# ETHERUNO.net
KiCad netlist of a schematic drawn in EAGLE
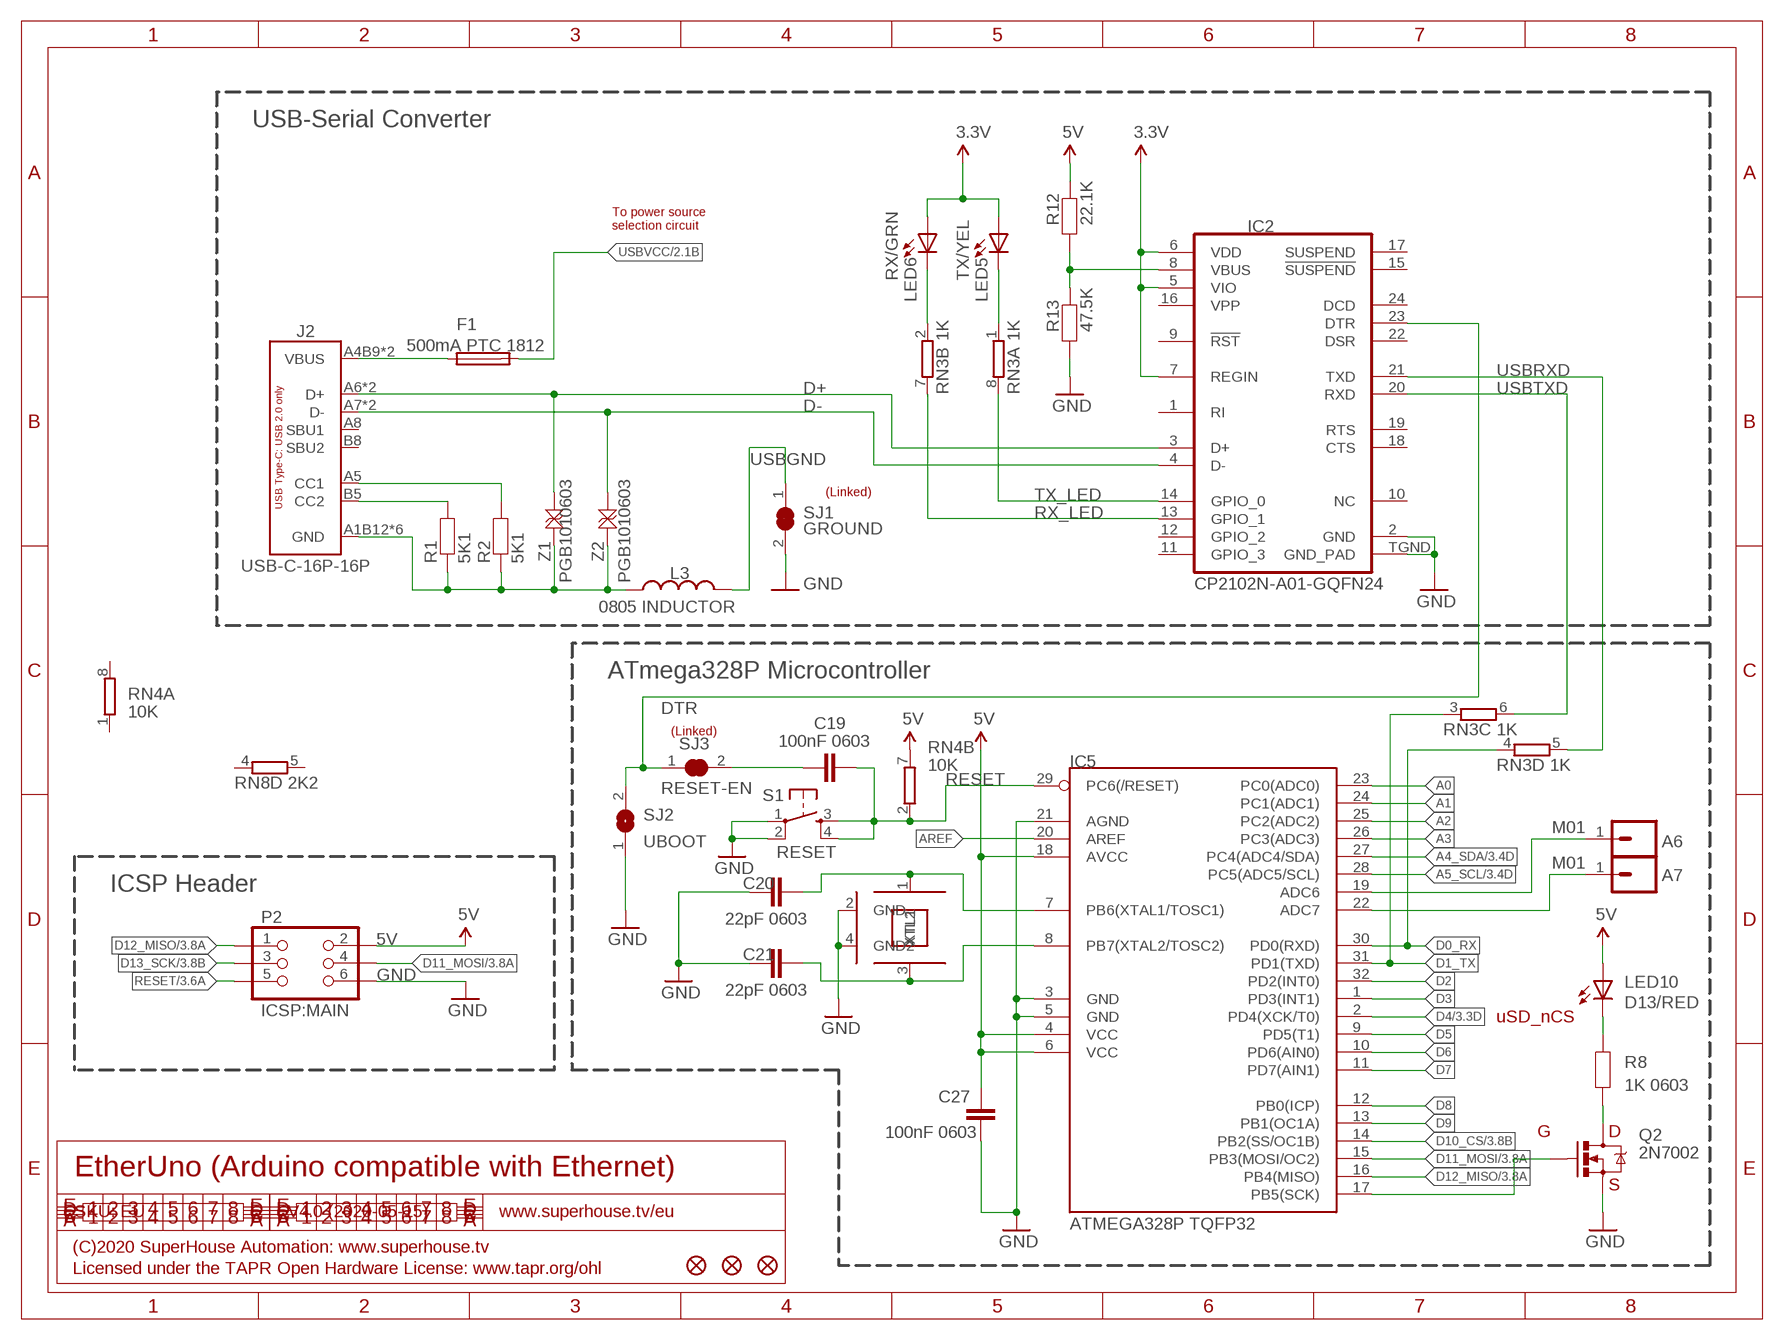
[diagram p0: schematic, sheet 1]
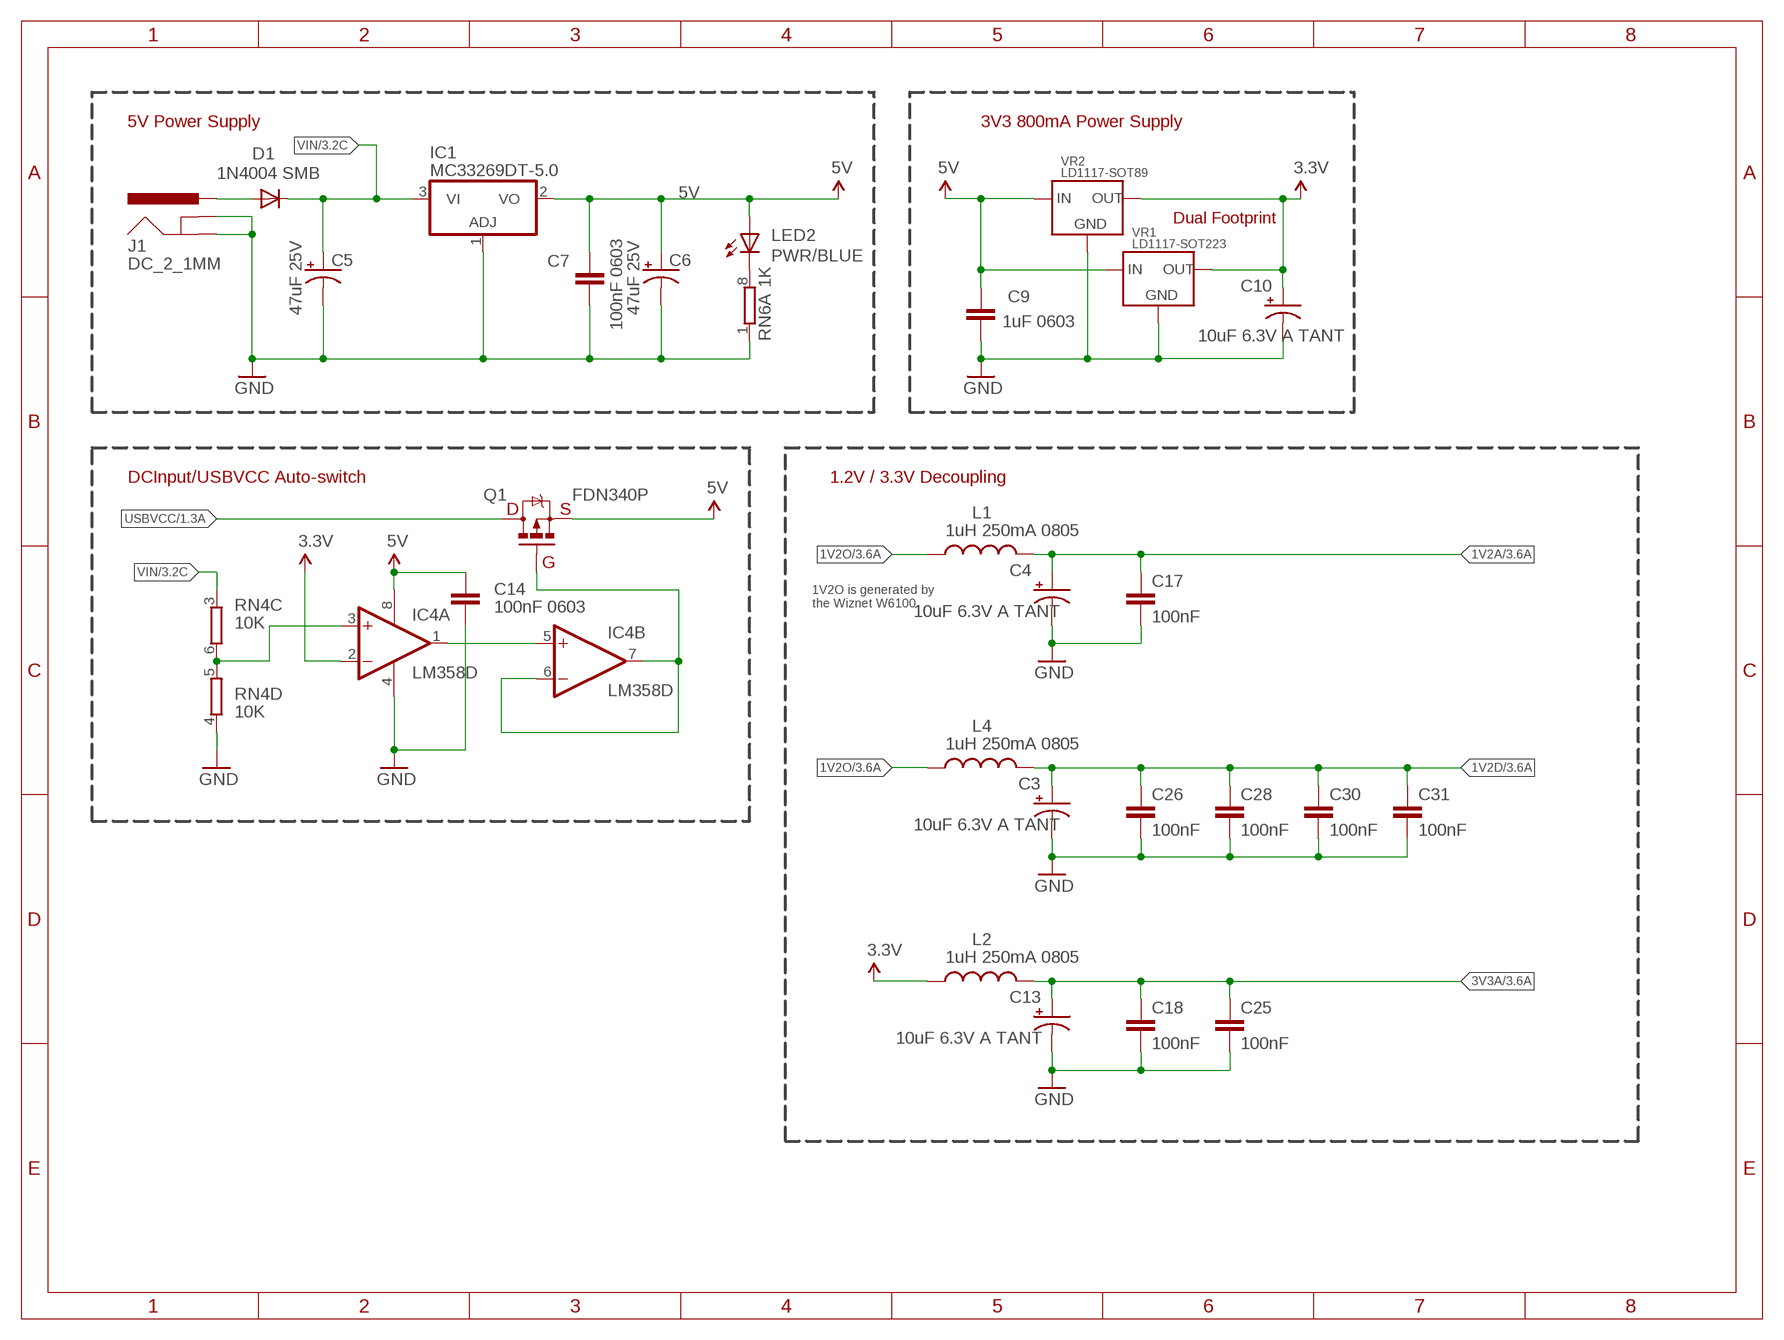
[diagram p1: schematic, sheet 2]
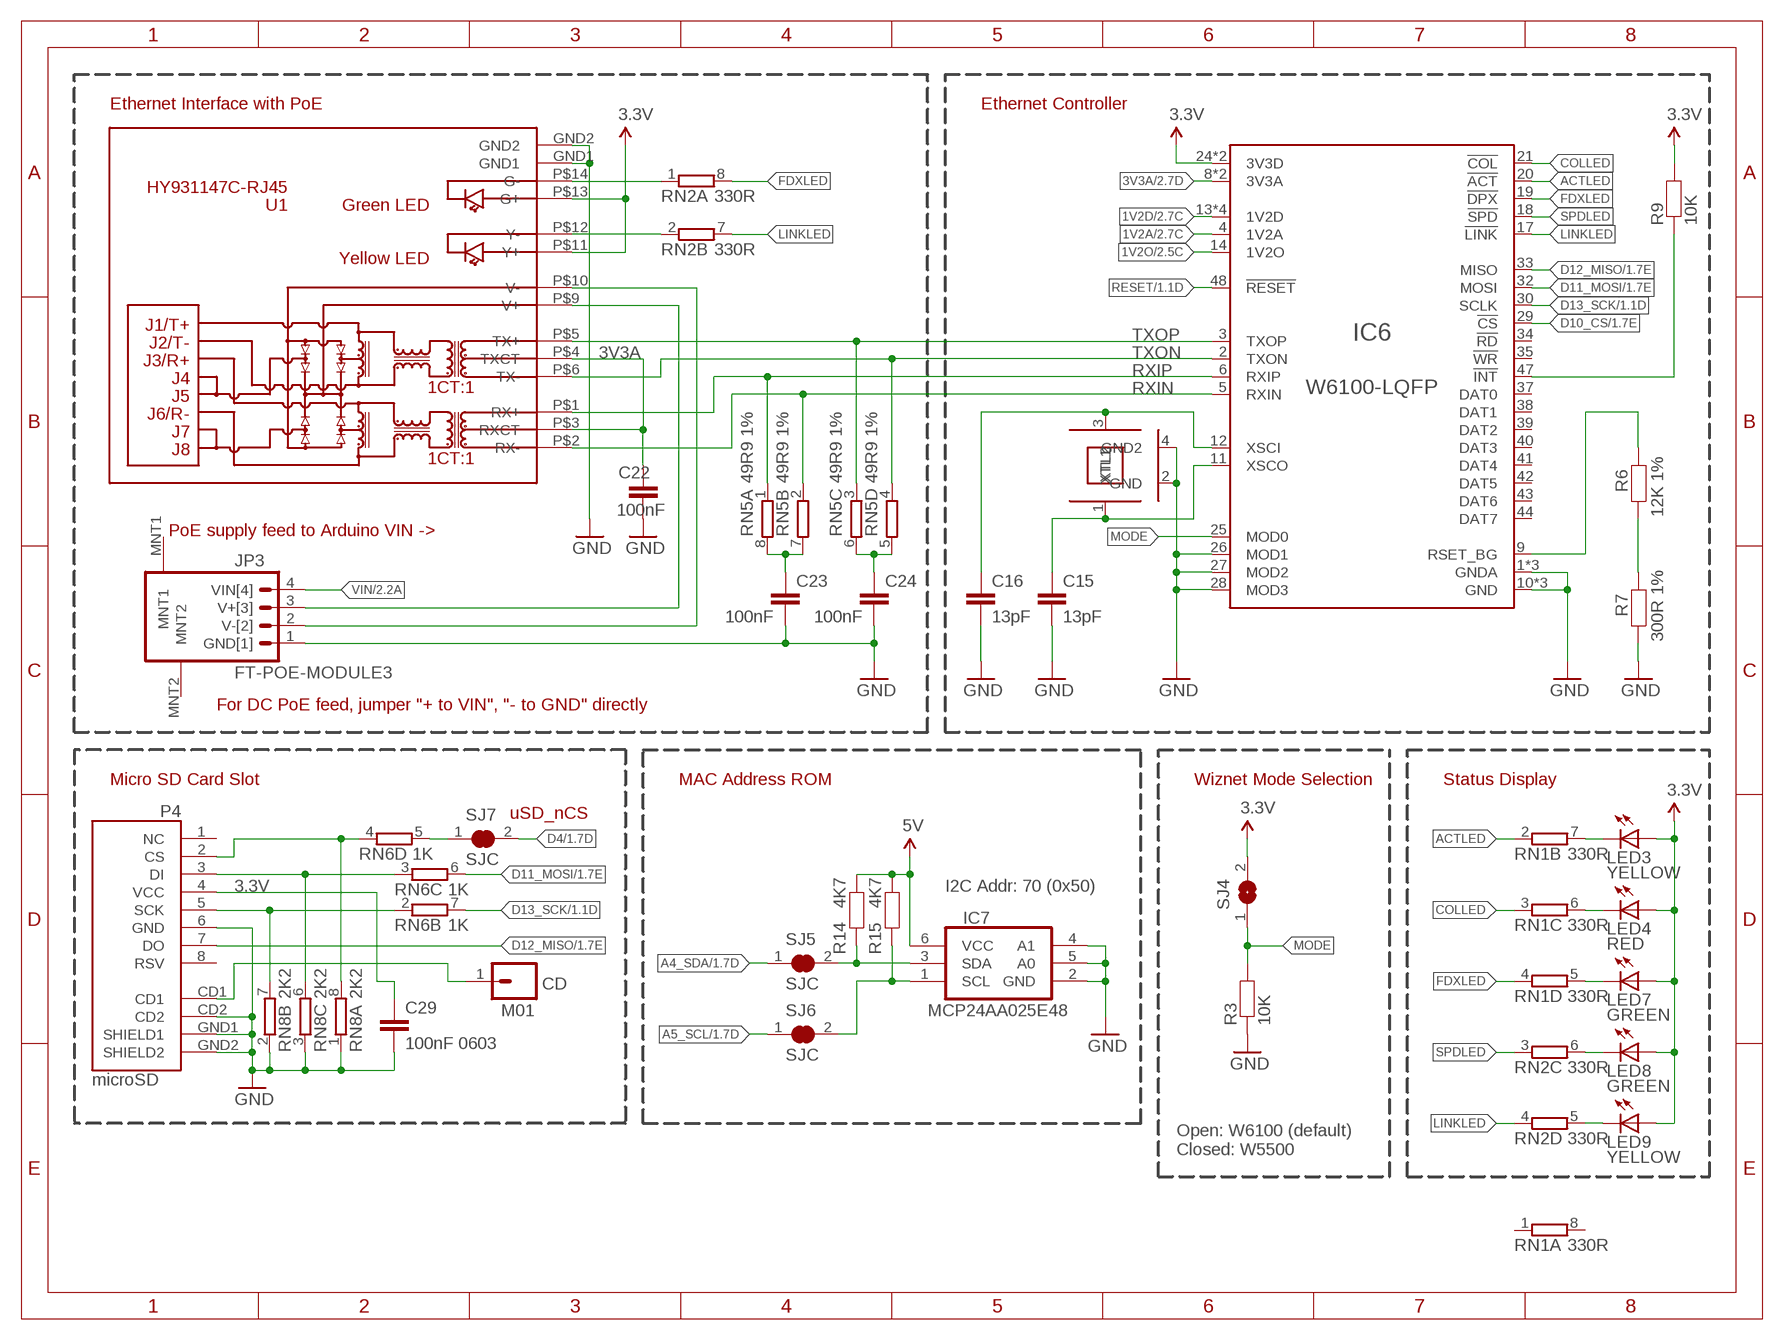
[diagram p2: schematic, sheet 3]
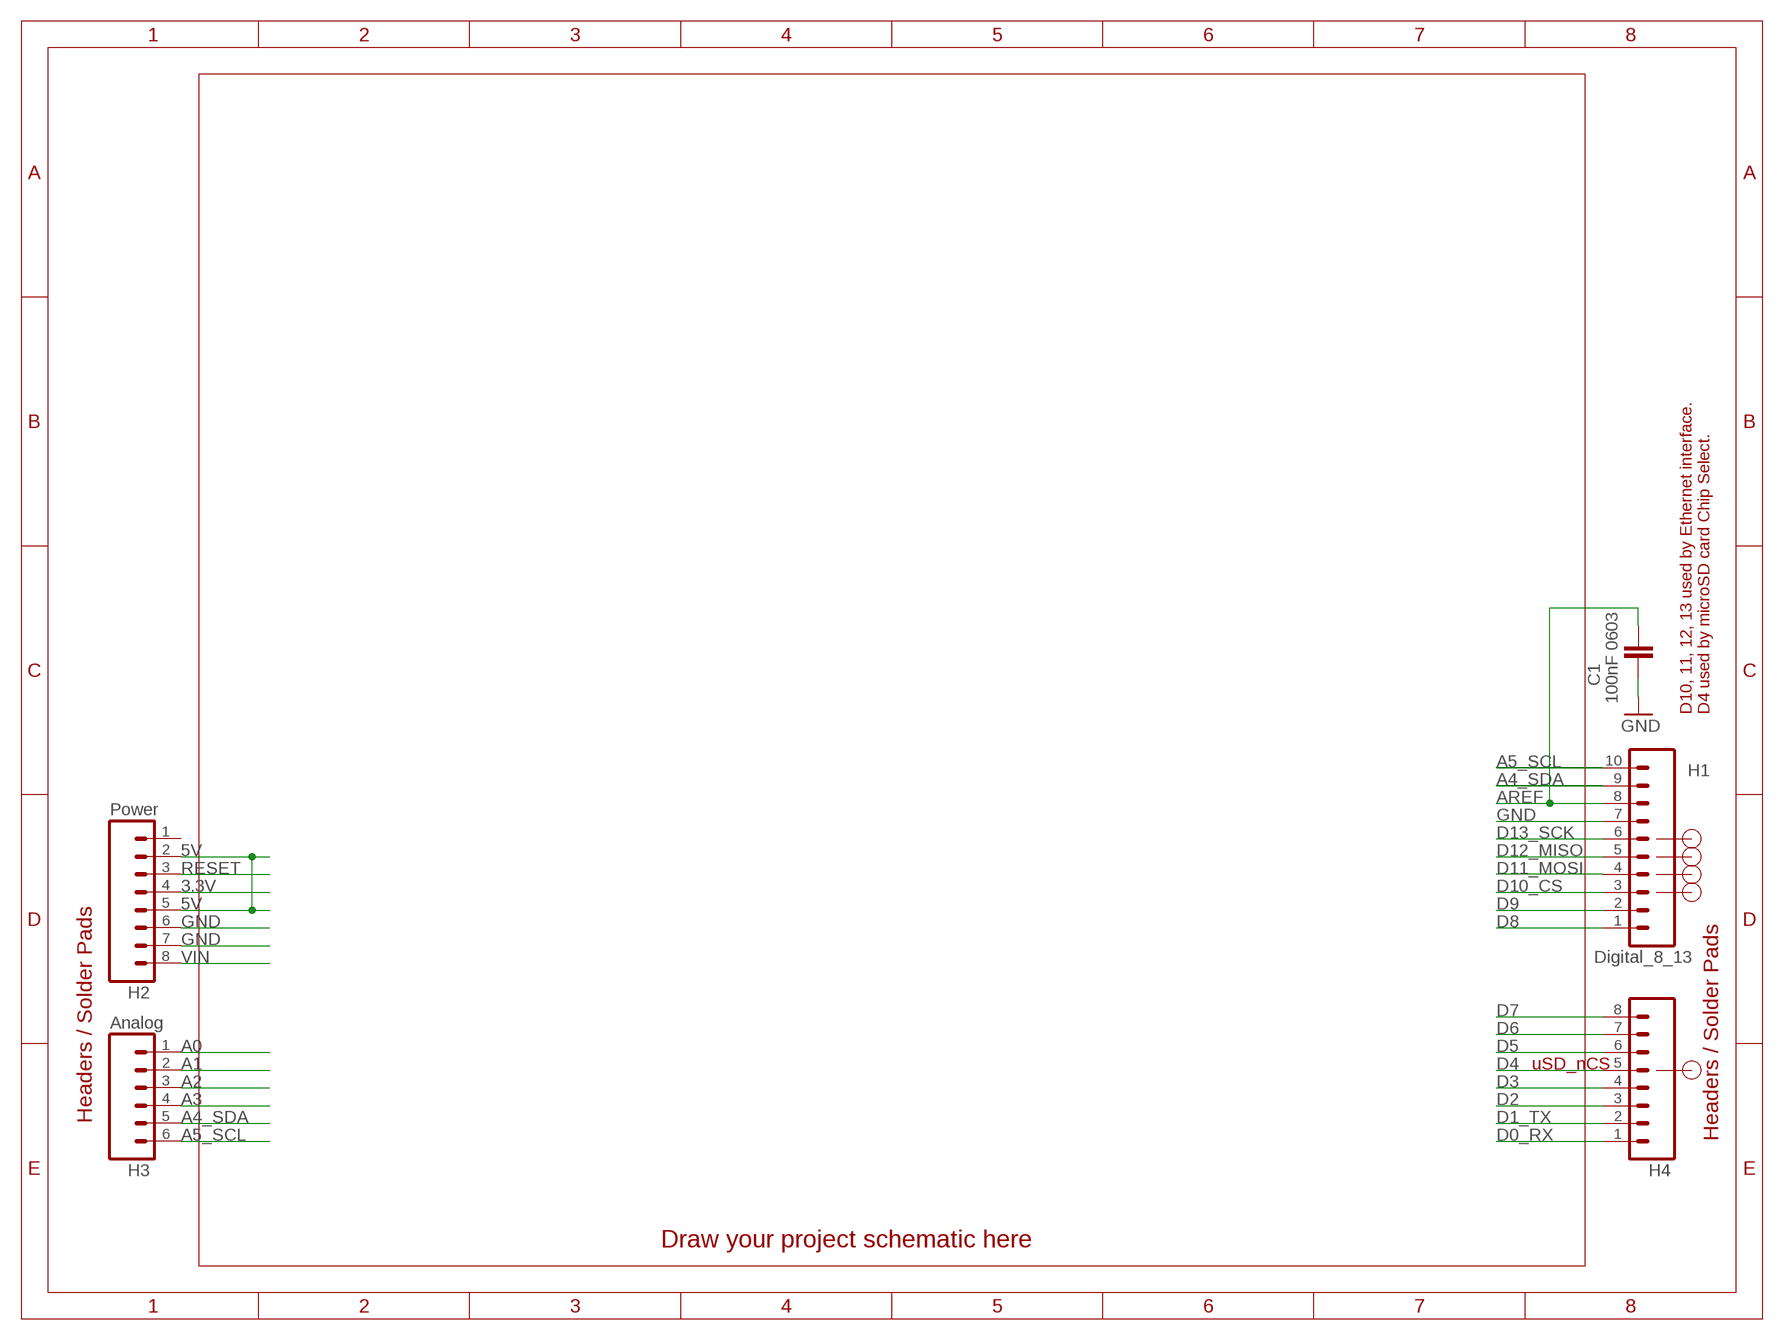
[diagram p3: schematic, sheet 4]

(export (version "E")
  (design (tool "Eeschema 10.0.6"))
  (components
    (comp (ref "A6")
      (value "M01")
      (footprint "eagle-import:1X01")
      (libsource (lib "eagle-import") (part "M01-PLAIN"))
    )
    (comp (ref "A7")
      (value "M01")
      (footprint "eagle-import:1X01")
      (libsource (lib "eagle-import") (part "M01-PLAIN"))
    )
    (comp (ref "C19")
      (value "100nF 0603")
      (footprint "eagle-import:C0603")
      (libsource (lib "eagle-import") (part "CAP0603"))
    )
    (comp (ref "C20")
      (value "22pF 0603")
      (footprint "eagle-import:C0603")
      (libsource (lib "eagle-import") (part "CAP0603"))
    )
    (comp (ref "C21")
      (value "22pF 0603")
      (footprint "eagle-import:C0603")
      (libsource (lib "eagle-import") (part "CAP0603"))
    )
    (comp (ref "C27")
      (value "100nF 0603")
      (footprint "eagle-import:C0603")
      (libsource (lib "eagle-import") (part "CAP0603"))
    )
    (comp (ref "F1")
      (value "500mA PTC 1812")
      (footprint "eagle-import:1812")
      (libsource (lib "eagle-import") (part "PTC050"))
    )
    (comp (ref "FID1")
      (value "FIDUCIAL1X2.5")
      (footprint "eagle-import:FIDUCIAL-1X2.5")
      (libsource (lib "eagle-import") (part "FIDUCIAL1X2.5"))
    )
    (comp (ref "FID2")
      (value "FIDUCIAL1X2.5")
      (footprint "eagle-import:FIDUCIAL-1X2.5")
      (libsource (lib "eagle-import") (part "FIDUCIAL1X2.5"))
    )
    (comp (ref "FID3")
      (value "FIDUCIAL1X2.5")
      (footprint "eagle-import:FIDUCIAL-1X2.5")
      (libsource (lib "eagle-import") (part "FIDUCIAL1X2.5"))
    )
    (comp (ref "IC2")
      (value "CP2102N-A01-GQFN24")
      (footprint "eagle-import:QFN-24")
      (libsource (lib "eagle-import") (part "CP2104"))
    )
    (comp (ref "IC5")
      (value "ATMEGA328P TQFP32")
      (footprint "eagle-import:TQFP32-08")
      (libsource (lib "eagle-import") (part "ATMEGA8-AI"))
    )
    (comp (ref "J2")
      (value "USB-C-16P-16P")
      (footprint "eagle-import:USB-C-16P")
      (libsource (lib "eagle-import") (part "USB-C-16P-16P"))
    )
    (comp (ref "L3")
      (value "0805 INDUCTOR")
      (footprint "eagle-import:0805-LARGE")
      (libsource (lib "eagle-import") (part "INDUCTOR0805-LARGE"))
    )
    (comp (ref "LED5")
      (value "TX/YEL")
      (footprint "eagle-import:LED-0603")
      (libsource (lib "eagle-import") (part "LED0603"))
    )
    (comp (ref "LED6")
      (value "RX/GRN")
      (footprint "eagle-import:LED-0603")
      (libsource (lib "eagle-import") (part "LED0603"))
    )
    (comp (ref "LED10")
      (value "D13/RED")
      (footprint "eagle-import:LED-0603")
      (libsource (lib "eagle-import") (part "LED0603"))
    )
    (comp (ref "P2")
      (value "ICSP:MAIN")
      (footprint "eagle-import:2X03-ICSP")
      (libsource (lib "eagle-import") (part "ICSP-PIN"))
    )
    (comp (ref "Q2")
      (value "2N7002")
      (footprint "eagle-import:SOT23-3")
      (libsource (lib "eagle-import") (part "MOSFET-NCHANNEL-233"))
    )
    (comp (ref "R1")
      (value "5K1")
      (footprint "eagle-import:R0603")
      (libsource (lib "eagle-import") (part "RESISTOR0603"))
    )
    (comp (ref "R2")
      (value "5K1")
      (footprint "eagle-import:R0603")
      (libsource (lib "eagle-import") (part "RESISTOR0603"))
    )
    (comp (ref "R8")
      (value "1K 0603")
      (footprint "eagle-import:R0603")
      (libsource (lib "eagle-import") (part "RESISTOR0603"))
    )
    (comp (ref "R12")
      (value "22.1K")
      (footprint "eagle-import:R0603")
      (libsource (lib "eagle-import") (part "RESISTOR0603"))
    )
    (comp (ref "R13")
      (value "47.5K")
      (footprint "eagle-import:R0603")
      (libsource (lib "eagle-import") (part "RESISTOR0603"))
    )
    (comp (ref "RN3")
      (value "1K")
      (footprint "eagle-import:CAY16")
      (libsource (lib "eagle-import") (part "4R-NCAY16"))
    )
    (comp (ref "RN4")
      (value "10K")
      (footprint "eagle-import:CAY16")
      (libsource (lib "eagle-import") (part "4R-NCAY16"))
    )
    (comp (ref "RN8")
      (value "2K2")
      (footprint "eagle-import:CAY16")
      (libsource (lib "eagle-import") (part "4R-NCAY16"))
    )
    (comp (ref "S1")
      (value "RESET")
      (footprint "eagle-import:TACTILE_SMT-6MM")
      (libsource (lib "eagle-import") (part "TAC_SWITCH-SMT-6"))
    )
    (comp (ref "SJ1")
      (value "GROUND")
      (footprint "eagle-import:SJC")
      (libsource (lib "eagle-import") (part "SJC-NORMAL"))
    )
    (comp (ref "SJ2")
      (value "UBOOT")
      (footprint "eagle-import:SJ")
      (libsource (lib "eagle-import") (part "SJ-NORMAL"))
    )
    (comp (ref "SJ3")
      (value "RESET-EN")
      (footprint "eagle-import:SJC")
      (libsource (lib "eagle-import") (part "SJC-NORMAL"))
    )
    (comp (ref "U$19")
      (value "CRYSTAL-GND3X2")
      (footprint "eagle-import:CRYSTAL-SMD-3X2")
      (libsource (lib "eagle-import") (part "CRYSTAL-GND3X2"))
    )
    (comp (ref "Z1")
      (value "PGB1010603")
      (footprint "eagle-import:TVS0603")
      (libsource (lib "eagle-import") (part "TVS0603"))
    )
    (comp (ref "Z2")
      (value "PGB1010603")
      (footprint "eagle-import:TVS0603")
      (libsource (lib "eagle-import") (part "TVS0603"))
    )
    (comp (ref "C1")
      (value "100nF 0603")
      (footprint "eagle-import:C0603")
      (libsource (lib "eagle-import") (part "CAP0603"))
    )
    (comp (ref "H1")
      (value "Digital_8_13")
      (footprint "eagle-import:1X10-S")
      (libsource (lib "eagle-import") (part "M10-SOCKET"))
    )
    (comp (ref "H2")
      (value "Power")
      (footprint "eagle-import:1X08-S")
      (libsource (lib "eagle-import") (part "M08-SOCKET"))
    )
    (comp (ref "H3")
      (value "Analog")
      (footprint "eagle-import:1X06-S")
      (libsource (lib "eagle-import") (part "M06-SOCKET"))
    )
    (comp (ref "H4")
      (value "Digital_0_7")
      (footprint "eagle-import:1X08-S")
      (libsource (lib "eagle-import") (part "M08-SOCKET"))
    )
    (comp (ref "C3")
      (value "10uF 6.3V A TANT")
      (footprint "eagle-import:EIA3216")
      (libsource (lib "eagle-import") (part "CAP_POL1206"))
    )
    (comp (ref "C4")
      (value "10uF 6.3V A TANT")
      (footprint "eagle-import:EIA3216")
      (libsource (lib "eagle-import") (part "CAP_POL1206"))
    )
    (comp (ref "C5")
      (value "47uF 25V")
      (footprint "eagle-import:PANASONIC_D")
      (libsource (lib "eagle-import") (part "CAP_POLD"))
    )
    (comp (ref "C6")
      (value "47uF 25V")
      (footprint "eagle-import:PANASONIC_D")
      (libsource (lib "eagle-import") (part "CAP_POLD"))
    )
    (comp (ref "C7")
      (value "100nF 0603")
      (footprint "eagle-import:C0603")
      (libsource (lib "eagle-import") (part "CAP0603"))
    )
    (comp (ref "C9")
      (value "1uF 0603")
      (footprint "eagle-import:C0603")
      (libsource (lib "eagle-import") (part "CAP0603"))
    )
    (comp (ref "C10")
      (value "10uF 6.3V A TANT")
      (footprint "eagle-import:EIA3216")
      (libsource (lib "eagle-import") (part "CAP_POL1206"))
    )
    (comp (ref "C13")
      (value "10uF 6.3V A TANT")
      (footprint "eagle-import:EIA3216")
      (libsource (lib "eagle-import") (part "CAP_POL1206"))
    )
    (comp (ref "C14")
      (value "100nF 0603")
      (footprint "eagle-import:C0603")
      (libsource (lib "eagle-import") (part "CAP0603"))
    )
    (comp (ref "C17")
      (value "100nF")
      (footprint "eagle-import:C0603")
      (libsource (lib "eagle-import") (part "CAP0603"))
    )
    (comp (ref "C18")
      (value "100nF")
      (footprint "eagle-import:C0603")
      (libsource (lib "eagle-import") (part "CAP0603"))
    )
    (comp (ref "C25")
      (value "100nF")
      (footprint "eagle-import:C0603")
      (libsource (lib "eagle-import") (part "CAP0603"))
    )
    (comp (ref "C26")
      (value "100nF")
      (footprint "eagle-import:C0603")
      (libsource (lib "eagle-import") (part "CAP0603"))
    )
    (comp (ref "C28")
      (value "100nF")
      (footprint "eagle-import:C0603")
      (libsource (lib "eagle-import") (part "CAP0603"))
    )
    (comp (ref "C30")
      (value "100nF")
      (footprint "eagle-import:C0603")
      (libsource (lib "eagle-import") (part "CAP0603"))
    )
    (comp (ref "C31")
      (value "100nF")
      (footprint "eagle-import:C0603")
      (libsource (lib "eagle-import") (part "CAP0603"))
    )
    (comp (ref "D1")
      (value "1N4004 SMB")
      (footprint "eagle-import:SMA-DIODE")
      (libsource (lib "eagle-import") (part "DIODESMA"))
    )
    (comp (ref "IC1")
      (value "MC33269DT-5.0")
      (footprint "eagle-import:DPACK")
      (libsource (lib "eagle-import") (part "MC33269-X-D-5.0"))
    )
    (comp (ref "IC4")
      (value "LM358D")
      (footprint "eagle-import:SO08")
      (libsource (lib "eagle-import") (part "LM358D"))
    )
    (comp (ref "J1")
      (value "DC_2_1MM")
      (footprint "eagle-import:POWER_JACK_SLOTS")
      (libsource (lib "eagle-import") (part "POWER_JACK-SLOTS"))
    )
    (comp (ref "L1")
      (value "1uH 250mA 0805")
      (footprint "eagle-import:0805-LARGE")
      (libsource (lib "eagle-import") (part "INDUCTOR0805-LARGE"))
    )
    (comp (ref "L2")
      (value "1uH 250mA 0805")
      (footprint "eagle-import:0805-LARGE")
      (libsource (lib "eagle-import") (part "INDUCTOR0805-LARGE"))
    )
    (comp (ref "L4")
      (value "1uH 250mA 0805")
      (footprint "eagle-import:0805-LARGE")
      (libsource (lib "eagle-import") (part "INDUCTOR0805-LARGE"))
    )
    (comp (ref "LED2")
      (value "PWR/BLUE")
      (footprint "eagle-import:LED-0603")
      (libsource (lib "eagle-import") (part "LED0603"))
    )
    (comp (ref "Q1")
      (value "FDN340P")
      (footprint "eagle-import:SOT23")
      (libsource (lib "eagle-import") (part "MOSFET-PCHANNEL"))
    )
    (comp (ref "RN6")
      (value "1K")
      (footprint "eagle-import:CAY16")
      (libsource (lib "eagle-import") (part "4R-NCAY16"))
    )
    (comp (ref "VR1")
      (value "LD1117-SOT223")
      (footprint "eagle-import:SOT-223")
      (libsource (lib "eagle-import") (part "LD1117-SOT223"))
    )
    (comp (ref "VR2")
      (value "LD1117-SOT89")
      (footprint "eagle-import:SOT89")
      (libsource (lib "eagle-import") (part "LD1117-SOT89"))
    )
    (comp (ref "C15")
      (value "13pF")
      (footprint "eagle-import:C0603")
      (libsource (lib "eagle-import") (part "CAP0603"))
    )
    (comp (ref "C16")
      (value "13pF")
      (footprint "eagle-import:C0603")
      (libsource (lib "eagle-import") (part "CAP0603"))
    )
    (comp (ref "C22")
      (value "100nF")
      (footprint "eagle-import:C0603")
      (libsource (lib "eagle-import") (part "CAP0603"))
    )
    (comp (ref "C23")
      (value "100nF")
      (footprint "eagle-import:C0603")
      (libsource (lib "eagle-import") (part "CAP0603"))
    )
    (comp (ref "C24")
      (value "100nF")
      (footprint "eagle-import:C0603")
      (libsource (lib "eagle-import") (part "CAP0603"))
    )
    (comp (ref "C29")
      (value "100nF 0603")
      (footprint "eagle-import:C0603")
      (libsource (lib "eagle-import") (part "CAP0603"))
    )
    (comp (ref "CD")
      (value "M01")
      (footprint "eagle-import:1X01")
      (libsource (lib "eagle-import") (part "M01-PLAIN"))
    )
    (comp (ref "IC6")
      (value "W6100-LQFP")
      (footprint "eagle-import:LQFP48")
      (libsource (lib "eagle-import") (part "W6100-LQFP"))
    )
    (comp (ref "IC7")
      (value "MCP24AA025E48")
      (footprint "eagle-import:SOT23-6")
      (libsource (lib "eagle-import") (part "MCP24AA025E48"))
    )
    (comp (ref "JP3")
      (value "FT-POE-MODULE3")
      (footprint "eagle-import:FT-POE-MODULE-NOLABEL")
      (libsource (lib "eagle-import") (part "FT-POE-MODULE3"))
    )
    (comp (ref "LED3")
      (value "YELLOW")
      (footprint "eagle-import:LED-0603")
      (libsource (lib "eagle-import") (part "LED0603"))
    )
    (comp (ref "LED4")
      (value "RED")
      (footprint "eagle-import:LED-0603")
      (libsource (lib "eagle-import") (part "LED0603"))
    )
    (comp (ref "LED7")
      (value "GREEN")
      (footprint "eagle-import:LED-0603")
      (libsource (lib "eagle-import") (part "LED0603"))
    )
    (comp (ref "LED8")
      (value "GREEN")
      (footprint "eagle-import:LED-0603")
      (libsource (lib "eagle-import") (part "LED0603"))
    )
    (comp (ref "LED9")
      (value "YELLOW")
      (footprint "eagle-import:LED-0603")
      (libsource (lib "eagle-import") (part "LED0603"))
    )
    (comp (ref "P4")
      (value "microSD")
      (footprint "eagle-import:MICRO-SD-SOCKET-PP")
      (libsource (lib "eagle-import") (part "USD-SOCKETNEW"))
    )
    (comp (ref "R3")
      (value "10K")
      (footprint "eagle-import:R0603")
      (libsource (lib "eagle-import") (part "RESISTOR0603"))
    )
    (comp (ref "R6")
      (value "12K 1%")
      (footprint "eagle-import:R0603")
      (libsource (lib "eagle-import") (part "RESISTOR0603"))
    )
    (comp (ref "R7")
      (value "300R 1%")
      (footprint "eagle-import:R0603")
      (libsource (lib "eagle-import") (part "RESISTOR0603"))
    )
    (comp (ref "R9")
      (value "10K")
      (footprint "eagle-import:R0603")
      (libsource (lib "eagle-import") (part "RESISTOR0603"))
    )
    (comp (ref "R14")
      (value "4K7")
      (footprint "eagle-import:R0603")
      (libsource (lib "eagle-import") (part "RESISTOR0603"))
    )
    (comp (ref "R15")
      (value "4K7")
      (footprint "eagle-import:R0603")
      (libsource (lib "eagle-import") (part "RESISTOR0603"))
    )
    (comp (ref "RN1")
      (value "330R")
      (footprint "eagle-import:CAY16")
      (libsource (lib "eagle-import") (part "4R-NCAY16"))
    )
    (comp (ref "RN2")
      (value "330R")
      (footprint "eagle-import:CAY16")
      (libsource (lib "eagle-import") (part "4R-NCAY16"))
    )
    (comp (ref "RN5")
      (value "49R9 1%")
      (footprint "eagle-import:CAY16")
      (libsource (lib "eagle-import") (part "4R-NCAY16"))
    )
    (comp (ref "SJ4")
      (value "SJ-NORMAL")
      (footprint "eagle-import:SJ")
      (libsource (lib "eagle-import") (part "SJ-NORMAL"))
    )
    (comp (ref "SJ5")
      (value "SJC")
      (footprint "eagle-import:SJC")
      (libsource (lib "eagle-import") (part "SJC-NORMAL"))
    )
    (comp (ref "SJ6")
      (value "SJC")
      (footprint "eagle-import:SJC")
      (libsource (lib "eagle-import") (part "SJC-NORMAL"))
    )
    (comp (ref "SJ7")
      (value "SJC")
      (footprint "eagle-import:SJC")
      (libsource (lib "eagle-import") (part "SJC-NORMAL"))
    )
    (comp (ref "U$17")
      (value "CRYSTAL-GND3X2")
      (footprint "eagle-import:CRYSTAL-SMD-3X2")
      (libsource (lib "eagle-import") (part "CRYSTAL-GND3X2"))
    )
    (comp (ref "U1")
      (value "HY931147C-RJ45")
      (footprint "eagle-import:HY931147C")
      (libsource (lib "eagle-import") (part "HY931147C-RJ45"))
    )
  )
  (nets
    (net (code "1") (name "1V2A") (class "Default")
      (node (ref "C17") (pin "1") (pinfunction "1_1") (pintype "passive"))
      (node (ref "C4") (pin "A") (pinfunction "+_A") (pintype "passive"))
      (node (ref "IC6") (pin "4") (pinfunction "1V2A_4") (pintype "bidirectional"))
      (node (ref "L1") (pin "2") (pinfunction "2_2") (pintype "passive"))
    )
    (net (code "2") (name "1V2D") (class "Default")
      (node (ref "C26") (pin "1") (pinfunction "1_1") (pintype "passive"))
      (node (ref "C28") (pin "1") (pinfunction "1_1") (pintype "passive"))
      (node (ref "C3") (pin "A") (pinfunction "+_A") (pintype "passive"))
      (node (ref "C30") (pin "1") (pinfunction "1_1") (pintype "passive"))
      (node (ref "C31") (pin "1") (pinfunction "1_1") (pintype "passive"))
      (node (ref "IC6") (pin "13") (pinfunction "1V2D_13") (pintype "bidirectional"))
      (node (ref "IC6") (pin "22") (pinfunction "1V2D_22") (pintype "bidirectional"))
      (node (ref "IC6") (pin "31") (pinfunction "1V2D_31") (pintype "bidirectional"))
      (node (ref "IC6") (pin "45") (pinfunction "1V2D_45") (pintype "bidirectional"))
      (node (ref "L4") (pin "2") (pinfunction "2_2") (pintype "passive"))
    )
    (net (code "3") (name "1V2O") (class "Default")
      (node (ref "IC6") (pin "14") (pinfunction "1V2O_14") (pintype "bidirectional"))
      (node (ref "L1") (pin "1") (pinfunction "1_1") (pintype "passive"))
      (node (ref "L4") (pin "1") (pinfunction "1_1") (pintype "passive"))
    )
    (net (code "4") (name "3.3V") (class "Default")
      (node (ref "C10") (pin "A") (pinfunction "+_A") (pintype "passive"))
      (node (ref "C29") (pin "1") (pinfunction "1_1") (pintype "passive"))
      (node (ref "H2") (pin "4") (pinfunction "4_4") (pintype "passive"))
      (node (ref "IC2") (pin "5") (pinfunction "VIO_5") (pintype "bidirectional"))
      (node (ref "IC2") (pin "6") (pinfunction "VDD_6") (pintype "power_in"))
      (node (ref "IC2") (pin "7") (pinfunction "REGIN_7") (pintype "power_in"))
      (node (ref "IC4") (pin "2") (pinfunction "-IN_2") (pintype "input"))
      (node (ref "IC6") (pin "24") (pinfunction "3V3D_24") (pintype "bidirectional"))
      (node (ref "IC6") (pin "36") (pinfunction "3V3D_36") (pintype "bidirectional"))
      (node (ref "L2") (pin "1") (pinfunction "1_1") (pintype "passive"))
      (node (ref "LED3") (pin "A") (pinfunction "A_A") (pintype "passive"))
      (node (ref "LED4") (pin "A") (pinfunction "A_A") (pintype "passive"))
      (node (ref "LED5") (pin "A") (pinfunction "A_A") (pintype "passive"))
      (node (ref "LED6") (pin "A") (pinfunction "A_A") (pintype "passive"))
      (node (ref "LED7") (pin "A") (pinfunction "A_A") (pintype "passive"))
      (node (ref "LED8") (pin "A") (pinfunction "A_A") (pintype "passive"))
      (node (ref "LED9") (pin "A") (pinfunction "A_A") (pintype "passive"))
      (node (ref "P4") (pin "4") (pinfunction "VCC_4") (pintype "bidirectional"))
      (node (ref "R9") (pin "2") (pinfunction "2_2") (pintype "passive"))
      (node (ref "SJ4") (pin "2") (pinfunction "2_2") (pintype "passive"))
      (node (ref "U1") (pin "P$11") (pinfunction "Y+_P$11") (pintype "bidirectional"))
      (node (ref "U1") (pin "P$13") (pinfunction "G+_P$13") (pintype "bidirectional"))
      (node (ref "VR1") (pin "2") (pinfunction "OUT_2") (pintype "power_in"))
      (node (ref "VR1") (pin "4") (pinfunction "OUT_4") (pintype "power_in"))
      (node (ref "VR2") (pin "2") (pinfunction "OUT_2") (pintype "power_in"))
      (node (ref "VR2") (pin "4") (pinfunction "OUT_4") (pintype "power_in"))
    )
    (net (code "5") (name "3V3A") (class "Default")
      (node (ref "C13") (pin "A") (pinfunction "+_A") (pintype "passive"))
      (node (ref "C18") (pin "1") (pinfunction "1_1") (pintype "passive"))
      (node (ref "C22") (pin "1") (pinfunction "1_1") (pintype "passive"))
      (node (ref "C25") (pin "1") (pinfunction "1_1") (pintype "passive"))
      (node (ref "IC6") (pin "15") (pinfunction "3V3A_15") (pintype "bidirectional"))
      (node (ref "IC6") (pin "8") (pinfunction "3V3A_8") (pintype "bidirectional"))
      (node (ref "L2") (pin "2") (pinfunction "2_2") (pintype "passive"))
      (node (ref "U1") (pin "P$3") (pinfunction "RXCT_P$3") (pintype "bidirectional"))
      (node (ref "U1") (pin "P$4") (pinfunction "TXCT_P$4") (pintype "bidirectional"))
    )
    (net (code "6") (name "5V") (class "Default")
      (node (ref "C14") (pin "1") (pinfunction "1_1") (pintype "passive"))
      (node (ref "C27") (pin "1") (pinfunction "1_1") (pintype "passive"))
      (node (ref "C6") (pin "+") (pinfunction "+_+") (pintype "passive"))
      (node (ref "C7") (pin "1") (pinfunction "1_1") (pintype "passive"))
      (node (ref "C9") (pin "1") (pinfunction "1_1") (pintype "passive"))
      (node (ref "H2") (pin "2") (pinfunction "2_2") (pintype "passive"))
      (node (ref "H2") (pin "5") (pinfunction "5_5") (pintype "passive"))
      (node (ref "IC1") (pin "2") (pinfunction "VO_2") (pintype "passive"))
      (node (ref "IC4") (pin "8") (pinfunction "V+_8") (pintype "power_in"))
      (node (ref "IC5") (pin "18") (pinfunction "AVCC_18") (pintype "bidirectional"))
      (node (ref "IC5") (pin "4") (pinfunction "VCC_4") (pintype "bidirectional"))
      (node (ref "IC5") (pin "6") (pinfunction "VCC_6") (pintype "bidirectional"))
      (node (ref "IC7") (pin "6") (pinfunction "VCC_6") (pintype "power_in"))
      (node (ref "LED10") (pin "A") (pinfunction "A_A") (pintype "passive"))
      (node (ref "LED2") (pin "A") (pinfunction "A_A") (pintype "passive"))
      (node (ref "P2") (pin "2") (pinfunction "2_2") (pintype "passive"))
      (node (ref "Q1") (pin "2") (pinfunction "S_2") (pintype "passive"))
      (node (ref "R12") (pin "2") (pinfunction "2_2") (pintype "passive"))
      (node (ref "R14") (pin "1") (pinfunction "1_1") (pintype "passive"))
      (node (ref "R15") (pin "1") (pinfunction "1_1") (pintype "passive"))
      (node (ref "RN4") (pin "7") (pinfunction "2_7") (pintype "passive"))
      (node (ref "VR1") (pin "3") (pinfunction "IN_3") (pintype "input"))
      (node (ref "VR2") (pin "3") (pinfunction "IN_3") (pintype "input"))
    )
    (net (code "7") (name "A0") (class "Default")
      (node (ref "H3") (pin "1") (pinfunction "1_1") (pintype "passive"))
      (node (ref "IC5") (pin "23") (pinfunction "PC0(ADC0)_23") (pintype "bidirectional"))
    )
    (net (code "8") (name "A1") (class "Default")
      (node (ref "H3") (pin "2") (pinfunction "2_2") (pintype "passive"))
      (node (ref "IC5") (pin "24") (pinfunction "PC1(ADC1)_24") (pintype "bidirectional"))
    )
    (net (code "9") (name "A2") (class "Default")
      (node (ref "H3") (pin "3") (pinfunction "3_3") (pintype "passive"))
      (node (ref "IC5") (pin "25") (pinfunction "PC2(ADC2)_25") (pintype "bidirectional"))
    )
    (net (code "10") (name "A3") (class "Default")
      (node (ref "H3") (pin "4") (pinfunction "4_4") (pintype "passive"))
      (node (ref "IC5") (pin "26") (pinfunction "PC3(ADC3)_26") (pintype "bidirectional"))
    )
    (net (code "11") (name "A4_SDA") (class "Default")
      (node (ref "H1") (pin "9") (pinfunction "9_9") (pintype "passive"))
      (node (ref "H3") (pin "5") (pinfunction "5_5") (pintype "passive"))
      (node (ref "IC5") (pin "27") (pinfunction "PC4(ADC4/SDA)_27") (pintype "bidirectional"))
      (node (ref "SJ5") (pin "1") (pinfunction "1_1") (pintype "passive"))
    )
    (net (code "12") (name "A5_SCL") (class "Default")
      (node (ref "H1") (pin "10") (pinfunction "10_10") (pintype "passive"))
      (node (ref "H3") (pin "6") (pinfunction "6_6") (pintype "passive"))
      (node (ref "IC5") (pin "28") (pinfunction "PC5(ADC5/SCL)_28") (pintype "bidirectional"))
      (node (ref "SJ6") (pin "1") (pinfunction "1_1") (pintype "passive"))
    )
    (net (code "13") (name "ACTLED") (class "Default")
      (node (ref "IC6") (pin "20") (pinfunction "~{ACT}_20") (pintype "bidirectional"))
      (node (ref "RN1") (pin "2") (pinfunction "1_2") (pintype "passive"))
    )
    (net (code "14") (name "AREF") (class "Default")
      (node (ref "C1") (pin "1") (pinfunction "1_1") (pintype "passive"))
      (node (ref "H1") (pin "8") (pinfunction "8_8") (pintype "passive"))
      (node (ref "IC5") (pin "20") (pinfunction "AREF_20") (pintype "bidirectional"))
    )
    (net (code "15") (name "COLLED") (class "Default")
      (node (ref "IC6") (pin "21") (pinfunction "~{COL}_21") (pintype "bidirectional"))
      (node (ref "RN1") (pin "3") (pinfunction "1_3") (pintype "passive"))
    )
    (net (code "16") (name "D+") (class "Default")
      (node (ref "IC2") (pin "3") (pinfunction "D+_3") (pintype "bidirectional"))
      (node (ref "J2") (pin "A6") (pinfunction "D+_A6") (pintype "bidirectional"))
      (node (ref "J2") (pin "B6") (pinfunction "D+_B6") (pintype "bidirectional"))
      (node (ref "Z1") (pin "1") (pinfunction "1_1") (pintype "passive"))
    )
    (net (code "17") (name "D-") (class "Default")
      (node (ref "IC2") (pin "4") (pinfunction "D-_4") (pintype "bidirectional"))
      (node (ref "J2") (pin "A7") (pinfunction "D-_A7") (pintype "bidirectional"))
      (node (ref "J2") (pin "B7") (pinfunction "D-_B7") (pintype "bidirectional"))
      (node (ref "Z2") (pin "1") (pinfunction "1_1") (pintype "passive"))
    )
    (net (code "18") (name "D0_RX") (class "Default")
      (node (ref "H4") (pin "1") (pinfunction "1_1") (pintype "passive"))
      (node (ref "IC5") (pin "30") (pinfunction "PD0(RXD)_30") (pintype "bidirectional"))
      (node (ref "RN3") (pin "4") (pinfunction "1_4") (pintype "passive"))
    )
    (net (code "19") (name "D1_TX") (class "Default")
      (node (ref "H4") (pin "2") (pinfunction "2_2") (pintype "passive"))
      (node (ref "IC5") (pin "31") (pinfunction "PD1(TXD)_31") (pintype "bidirectional"))
      (node (ref "RN3") (pin "3") (pinfunction "1_3") (pintype "passive"))
    )
    (net (code "20") (name "D2") (class "Default")
      (node (ref "H4") (pin "3") (pinfunction "3_3") (pintype "passive"))
      (node (ref "IC5") (pin "32") (pinfunction "PD2(INT0)_32") (pintype "bidirectional"))
    )
    (net (code "21") (name "D3") (class "Default")
      (node (ref "H4") (pin "4") (pinfunction "4_4") (pintype "passive"))
      (node (ref "IC5") (pin "1") (pinfunction "PD3(INT1)_1") (pintype "bidirectional"))
    )
    (net (code "22") (name "D4") (class "Default")
      (node (ref "H4") (pin "5") (pinfunction "5_5") (pintype "passive"))
      (node (ref "IC5") (pin "2") (pinfunction "PD4(XCK/T0)_2") (pintype "bidirectional"))
      (node (ref "SJ7") (pin "2") (pinfunction "2_2") (pintype "passive"))
    )
    (net (code "23") (name "D5") (class "Default")
      (node (ref "H4") (pin "6") (pinfunction "6_6") (pintype "passive"))
      (node (ref "IC5") (pin "9") (pinfunction "PD5(T1)_9") (pintype "bidirectional"))
    )
    (net (code "24") (name "D6") (class "Default")
      (node (ref "H4") (pin "7") (pinfunction "7_7") (pintype "passive"))
      (node (ref "IC5") (pin "10") (pinfunction "PD6(AIN0)_10") (pintype "bidirectional"))
    )
    (net (code "25") (name "D7") (class "Default")
      (node (ref "H4") (pin "8") (pinfunction "8_8") (pintype "passive"))
      (node (ref "IC5") (pin "11") (pinfunction "PD7(AIN1)_11") (pintype "bidirectional"))
    )
    (net (code "26") (name "D8") (class "Default")
      (node (ref "H1") (pin "1") (pinfunction "1_1") (pintype "passive"))
      (node (ref "IC5") (pin "12") (pinfunction "PB0(ICP)_12") (pintype "bidirectional"))
    )
    (net (code "27") (name "D9") (class "Default")
      (node (ref "H1") (pin "2") (pinfunction "2_2") (pintype "passive"))
      (node (ref "IC5") (pin "13") (pinfunction "PB1(OC1A)_13") (pintype "bidirectional"))
    )
    (net (code "28") (name "D10_CS") (class "Default")
      (node (ref "H1") (pin "3") (pinfunction "3_3") (pintype "passive"))
      (node (ref "IC5") (pin "14") (pinfunction "PB2(SS/OC1B)_14") (pintype "bidirectional"))
      (node (ref "IC6") (pin "29") (pinfunction "~{CS}_29") (pintype "bidirectional"))
    )
    (net (code "29") (name "D11_MOSI") (class "Default")
      (node (ref "H1") (pin "4") (pinfunction "4_4") (pintype "passive"))
      (node (ref "IC5") (pin "15") (pinfunction "PB3(MOSI/OC2)_15") (pintype "bidirectional"))
      (node (ref "IC6") (pin "32") (pinfunction "MOSI_32") (pintype "bidirectional"))
      (node (ref "P2") (pin "4") (pinfunction "4_4") (pintype "passive"))
      (node (ref "RN6") (pin "6") (pinfunction "2_6") (pintype "passive"))
    )
    (net (code "30") (name "D12_MISO") (class "Default")
      (node (ref "H1") (pin "5") (pinfunction "5_5") (pintype "passive"))
      (node (ref "IC5") (pin "16") (pinfunction "PB4(MISO)_16") (pintype "bidirectional"))
      (node (ref "IC6") (pin "33") (pinfunction "MISO_33") (pintype "bidirectional"))
      (node (ref "P2") (pin "1") (pinfunction "1_1") (pintype "passive"))
      (node (ref "P4") (pin "7") (pinfunction "DO_7") (pintype "bidirectional"))
    )
    (net (code "31") (name "D13_SCK") (class "Default")
      (node (ref "H1") (pin "6") (pinfunction "6_6") (pintype "passive"))
      (node (ref "IC5") (pin "17") (pinfunction "PB5(SCK)_17") (pintype "bidirectional"))
      (node (ref "IC6") (pin "30") (pinfunction "SCLK_30") (pintype "bidirectional"))
      (node (ref "P2") (pin "3") (pinfunction "3_3") (pintype "passive"))
      (node (ref "Q2") (pin "1") (pinfunction "G_1") (pintype "passive"))
      (node (ref "RN6") (pin "7") (pinfunction "2_7") (pintype "passive"))
    )
    (net (code "32") (name "DTR") (class "Default")
      (node (ref "IC2") (pin "23") (pinfunction "DTR_23") (pintype "output"))
      (node (ref "SJ2") (pin "2") (pinfunction "2_2") (pintype "passive"))
      (node (ref "SJ3") (pin "1") (pinfunction "1_1") (pintype "passive"))
    )
    (net (code "33") (name "FDXLED") (class "Default")
      (node (ref "IC6") (pin "19") (pinfunction "~{DPX}_19") (pintype "bidirectional"))
      (node (ref "RN1") (pin "4") (pinfunction "1_4") (pintype "passive"))
      (node (ref "RN2") (pin "8") (pinfunction "2_8") (pintype "passive"))
    )
    (net (code "34") (name "GND") (class "Default")
      (node (ref "C1") (pin "2") (pinfunction "2_2") (pintype "passive"))
      (node (ref "C10") (pin "C") (pinfunction "-_C") (pintype "passive"))
      (node (ref "C13") (pin "C") (pinfunction "-_C") (pintype "passive"))
      (node (ref "C14") (pin "2") (pinfunction "2_2") (pintype "passive"))
      (node (ref "C15") (pin "2") (pinfunction "2_2") (pintype "passive"))
      (node (ref "C16") (pin "2") (pinfunction "2_2") (pintype "passive"))
      (node (ref "C17") (pin "2") (pinfunction "2_2") (pintype "passive"))
      (node (ref "C18") (pin "2") (pinfunction "2_2") (pintype "passive"))
      (node (ref "C20") (pin "1") (pinfunction "1_1") (pintype "passive"))
      (node (ref "C21") (pin "1") (pinfunction "1_1") (pintype "passive"))
      (node (ref "C22") (pin "2") (pinfunction "2_2") (pintype "passive"))
      (node (ref "C23") (pin "2") (pinfunction "2_2") (pintype "passive"))
      (node (ref "C24") (pin "2") (pinfunction "2_2") (pintype "passive"))
      (node (ref "C25") (pin "2") (pinfunction "2_2") (pintype "passive"))
      (node (ref "C26") (pin "2") (pinfunction "2_2") (pintype "passive"))
      (node (ref "C27") (pin "2") (pinfunction "2_2") (pintype "passive"))
      (node (ref "C28") (pin "2") (pinfunction "2_2") (pintype "passive"))
      (node (ref "C29") (pin "2") (pinfunction "2_2") (pintype "passive"))
      (node (ref "C3") (pin "C") (pinfunction "-_C") (pintype "passive"))
      (node (ref "C30") (pin "2") (pinfunction "2_2") (pintype "passive"))
      (node (ref "C31") (pin "2") (pinfunction "2_2") (pintype "passive"))
      (node (ref "C4") (pin "C") (pinfunction "-_C") (pintype "passive"))
      (node (ref "C5") (pin "-") (pinfunction "-_-") (pintype "passive"))
      (node (ref "C6") (pin "-") (pinfunction "-_-") (pintype "passive"))
      (node (ref "C7") (pin "2") (pinfunction "2_2") (pintype "passive"))
      (node (ref "C9") (pin "2") (pinfunction "2_2") (pintype "passive"))
      (node (ref "H1") (pin "7") (pinfunction "7_7") (pintype "passive"))
      (node (ref "H2") (pin "6") (pinfunction "6_6") (pintype "passive"))
      (node (ref "H2") (pin "7") (pinfunction "7_7") (pintype "passive"))
      (node (ref "IC1") (pin "1") (pinfunction "ADJ_1") (pintype "input"))
      (node (ref "IC2") (pin "2") (pinfunction "GND_2") (pintype "power_in"))
      (node (ref "IC2") (pin "TGND") (pinfunction "GND_PAD_TGND") (pintype "power_in"))
      (node (ref "IC4") (pin "4") (pinfunction "V-_4") (pintype "power_in"))
      (node (ref "IC5") (pin "21") (pinfunction "AGND_21") (pintype "bidirectional"))
      (node (ref "IC5") (pin "3") (pinfunction "GND_3") (pintype "bidirectional"))
      (node (ref "IC5") (pin "5") (pinfunction "GND_5") (pintype "bidirectional"))
      (node (ref "IC6") (pin "1") (pinfunction "GNDA_1") (pintype "bidirectional"))
      (node (ref "IC6") (pin "10") (pinfunction "GND_10") (pintype "bidirectional"))
      (node (ref "IC6") (pin "16") (pinfunction "GNDA_16") (pintype "bidirectional"))
      (node (ref "IC6") (pin "23") (pinfunction "GND_23") (pintype "bidirectional"))
      (node (ref "IC6") (pin "26") (pinfunction "MOD1_26") (pintype "bidirectional"))
      (node (ref "IC6") (pin "27") (pinfunction "MOD2_27") (pintype "bidirectional"))
      (node (ref "IC6") (pin "28") (pinfunction "MOD3_28") (pintype "bidirectional"))
      (node (ref "IC6") (pin "46") (pinfunction "GND_46") (pintype "bidirectional"))
      (node (ref "IC6") (pin "7") (pinfunction "GNDA_7") (pintype "bidirectional"))
      (node (ref "IC7") (pin "2") (pinfunction "GND_2") (pintype "power_in"))
      (node (ref "IC7") (pin "4") (pinfunction "A1_4") (pintype "input"))
      (node (ref "IC7") (pin "5") (pinfunction "A0_5") (pintype "input"))
      (node (ref "J1") (pin "GND") (pinfunction "GND_GND") (pintype "bidirectional"))
      (node (ref "J1") (pin "GNDBREAK") (pinfunction "GNDBREAK_GNDBREAK") (pintype "bidirectional"))
      (node (ref "JP3") (pin "1") (pinfunction "GND[1]_1") (pintype "passive"))
      (node (ref "P2") (pin "6") (pinfunction "6_6") (pintype "passive"))
      (node (ref "P4") (pin "6") (pinfunction "GND_6") (pintype "bidirectional"))
      (node (ref "P4") (pin "CD2") (pinfunction "CD2_CD2") (pintype "bidirectional"))
      (node (ref "P4") (pin "GND1") (pinfunction "SHIELD1_GND1") (pintype "bidirectional"))
      (node (ref "P4") (pin "GND2") (pinfunction "SHIELD2_GND2") (pintype "bidirectional"))
      (node (ref "Q2") (pin "2") (pinfunction "S_2") (pintype "passive"))
      (node (ref "R13") (pin "1") (pinfunction "1_1") (pintype "passive"))
      (node (ref "R3") (pin "1") (pinfunction "1_1") (pintype "passive"))
      (node (ref "R7") (pin "2") (pinfunction "2_2") (pintype "passive"))
      (node (ref "RN4") (pin "4") (pinfunction "1_4") (pintype "passive"))
      (node (ref "RN6") (pin "1") (pinfunction "1_1") (pintype "passive"))
      (node (ref "RN8") (pin "1") (pinfunction "1_1") (pintype "passive"))
      (node (ref "RN8") (pin "2") (pinfunction "1_2") (pintype "passive"))
      (node (ref "RN8") (pin "3") (pinfunction "1_3") (pintype "passive"))
      (node (ref "S1") (pin "1") (pinfunction "1_1") (pintype "passive"))
      (node (ref "S1") (pin "2") (pinfunction "2_2") (pintype "passive"))
      (node (ref "SJ1") (pin "2") (pinfunction "2_2") (pintype "passive"))
      (node (ref "SJ2") (pin "1") (pinfunction "1_1") (pintype "passive"))
      (node (ref "U$17") (pin "2") (pinfunction "GND_2") (pintype "bidirectional"))
      (node (ref "U$17") (pin "4") (pinfunction "GND2_4") (pintype "bidirectional"))
      (node (ref "U$19") (pin "2") (pinfunction "GND_2") (pintype "bidirectional"))
      (node (ref "U$19") (pin "4") (pinfunction "GND2_4") (pintype "bidirectional"))
      (node (ref "U1") (pin "GND1") (pinfunction "GND1_GND1") (pintype "bidirectional"))
      (node (ref "U1") (pin "GND2") (pinfunction "GND2_GND2") (pintype "bidirectional"))
      (node (ref "VR1") (pin "1") (pinfunction "GND_1") (pintype "input"))
      (node (ref "VR2") (pin "1") (pinfunction "GND_1") (pintype "input"))
    )
    (net (code "35") (name "LINKLED") (class "Default")
      (node (ref "IC6") (pin "17") (pinfunction "~{LINK}_17") (pintype "bidirectional"))
      (node (ref "RN2") (pin "4") (pinfunction "1_4") (pintype "passive"))
      (node (ref "RN2") (pin "7") (pinfunction "2_7") (pintype "passive"))
    )
    (net (code "36") (name "MODE") (class "Default")
      (node (ref "IC6") (pin "25") (pinfunction "MOD0_25") (pintype "bidirectional"))
      (node (ref "R3") (pin "2") (pinfunction "2_2") (pintype "passive"))
      (node (ref "SJ4") (pin "1") (pinfunction "1_1") (pintype "passive"))
    )
    (net (code "37") (name "Net-(C19-Pad1)") (class "Default")
      (node (ref "C19") (pin "1") (pinfunction "1_1") (pintype "passive"))
      (node (ref "SJ3") (pin "2") (pinfunction "2_2") (pintype "passive"))
    )
    (net (code "38") (name "Net-(CD-Pad1)") (class "Default")
      (node (ref "CD") (pin "1") (pinfunction "1_1") (pintype "passive"))
      (node (ref "P4") (pin "CD1") (pinfunction "CD1_CD1") (pintype "bidirectional"))
    )
    (net (code "39") (name "Net-(D1-PadA)") (class "Default")
      (node (ref "D1") (pin "A") (pinfunction "A_A") (pintype "passive"))
      (node (ref "J1") (pin "PWR") (pinfunction "PWR_PWR") (pintype "bidirectional"))
    )
    (net (code "40") (name "Net-(F1-Pad1)") (class "Default")
      (node (ref "F1") (pin "1") (pinfunction "1_1") (pintype "passive"))
      (node (ref "J2") (pin "A4B9") (pinfunction "VBUS_A4B9") (pintype "power_in"))
      (node (ref "J2") (pin "A9B4") (pinfunction "VBUS_A9B4") (pintype "power_in"))
    )
    (net (code "41") (name "Net-(IC2-VBUS)") (class "Default")
      (node (ref "IC2") (pin "8") (pinfunction "VBUS_8") (pintype "bidirectional"))
      (node (ref "R12") (pin "1") (pinfunction "1_1") (pintype "passive"))
      (node (ref "R13") (pin "2") (pinfunction "2_2") (pintype "passive"))
    )
    (net (code "42") (name "Net-(IC4A-+IN)") (class "Default")
      (node (ref "IC4") (pin "3") (pinfunction "+IN_3") (pintype "input"))
      (node (ref "RN4") (pin "5") (pinfunction "2_5") (pintype "passive"))
      (node (ref "RN4") (pin "6") (pinfunction "2_6") (pintype "passive"))
    )
    (net (code "43") (name "Net-(IC4A-OUT)") (class "Default")
      (node (ref "IC4") (pin "1") (pinfunction "OUT_1") (pintype "output"))
      (node (ref "IC4") (pin "5") (pinfunction "+IN_5") (pintype "input"))
    )
    (net (code "44") (name "Net-(IC4B--IN)") (class "Default")
      (node (ref "IC4") (pin "6") (pinfunction "-IN_6") (pintype "input"))
      (node (ref "IC4") (pin "7") (pinfunction "OUT_7") (pintype "output"))
      (node (ref "Q1") (pin "1") (pinfunction "G_1") (pintype "passive"))
    )
    (net (code "45") (name "Net-(IC5-ADC6)") (class "Default")
      (node (ref "A6") (pin "1") (pinfunction "1_1") (pintype "passive"))
      (node (ref "IC5") (pin "19") (pinfunction "ADC6_19") (pintype "bidirectional"))
    )
    (net (code "46") (name "Net-(IC5-ADC7)") (class "Default")
      (node (ref "A7") (pin "1") (pinfunction "1_1") (pintype "passive"))
      (node (ref "IC5") (pin "22") (pinfunction "ADC7_22") (pintype "bidirectional"))
    )
    (net (code "47") (name "Net-(IC5-PB6(XTAL1{slash}TOSC1))") (class "Default")
      (node (ref "C20") (pin "2") (pinfunction "2_2") (pintype "passive"))
      (node (ref "IC5") (pin "7") (pinfunction "PB6(XTAL1/TOSC1)_7") (pintype "bidirectional"))
      (node (ref "U$19") (pin "1") (pinfunction "XTL1_1") (pintype "bidirectional"))
    )
    (net (code "48") (name "Net-(IC5-PB7(XTAL2{slash}TOSC2))") (class "Default")
      (node (ref "C21") (pin "2") (pinfunction "2_2") (pintype "passive"))
      (node (ref "IC5") (pin "8") (pinfunction "PB7(XTAL2/TOSC2)_8") (pintype "bidirectional"))
      (node (ref "U$19") (pin "3") (pinfunction "XTL2_3") (pintype "bidirectional"))
    )
    (net (code "49") (name "Net-(IC6-RSET_BG)") (class "Default")
      (node (ref "IC6") (pin "9") (pinfunction "RSET_BG_9") (pintype "bidirectional"))
      (node (ref "R6") (pin "1") (pinfunction "1_1") (pintype "passive"))
    )
    (net (code "50") (name "Net-(IC6-XSCI)") (class "Default")
      (node (ref "C16") (pin "1") (pinfunction "1_1") (pintype "passive"))
      (node (ref "IC6") (pin "12") (pinfunction "XSCI_12") (pintype "bidirectional"))
      (node (ref "U$17") (pin "3") (pinfunction "XTL2_3") (pintype "bidirectional"))
    )
    (net (code "51") (name "Net-(IC6-XSCO)") (class "Default")
      (node (ref "C15") (pin "1") (pinfunction "1_1") (pintype "passive"))
      (node (ref "IC6") (pin "11") (pinfunction "XSCO_11") (pintype "bidirectional"))
      (node (ref "U$17") (pin "1") (pinfunction "XTL1_1") (pintype "bidirectional"))
    )
    (net (code "52") (name "Net-(IC6-~{INT})") (class "Default")
      (node (ref "IC6") (pin "47") (pinfunction "~{INT}_47") (pintype "bidirectional"))
      (node (ref "R9") (pin "1") (pinfunction "1_1") (pintype "passive"))
    )
    (net (code "53") (name "Net-(IC7-SCL)") (class "Default")
      (node (ref "IC7") (pin "1") (pinfunction "SCL_1") (pintype "bidirectional"))
      (node (ref "R15") (pin "2") (pinfunction "2_2") (pintype "passive"))
      (node (ref "SJ6") (pin "2") (pinfunction "2_2") (pintype "passive"))
    )
    (net (code "54") (name "Net-(IC7-SDA)") (class "Default")
      (node (ref "IC7") (pin "3") (pinfunction "SDA_3") (pintype "bidirectional"))
      (node (ref "R14") (pin "2") (pinfunction "2_2") (pintype "passive"))
      (node (ref "SJ5") (pin "2") (pinfunction "2_2") (pintype "passive"))
    )
    (net (code "55") (name "Net-(J2-CC1)") (class "Default")
      (node (ref "J2") (pin "A5") (pinfunction "CC1_A5") (pintype "bidirectional"))
      (node (ref "R2") (pin "2") (pinfunction "2_2") (pintype "passive"))
    )
    (net (code "56") (name "Net-(J2-CC2)") (class "Default")
      (node (ref "J2") (pin "B5") (pinfunction "CC2_B5") (pintype "bidirectional"))
      (node (ref "R1") (pin "2") (pinfunction "2_2") (pintype "passive"))
    )
    (net (code "57") (name "Net-(J2-GND-PadA12B1)") (class "Default")
      (node (ref "J2") (pin "A12B1") (pinfunction "GND_A12B1") (pintype "power_in"))
      (node (ref "J2") (pin "A1B12") (pinfunction "GND_A1B12") (pintype "power_in"))
      (node (ref "J2") (pin "FIX1") (pinfunction "GND_FIX1") (pintype "power_in"))
      (node (ref "J2") (pin "FIX2") (pinfunction "GND_FIX2") (pintype "power_in"))
      (node (ref "J2") (pin "FIX3") (pinfunction "GND_FIX3") (pintype "power_in"))
      (node (ref "J2") (pin "FIX4") (pinfunction "GND_FIX4") (pintype "power_in"))
      (node (ref "L3") (pin "1") (pinfunction "1_1") (pintype "passive"))
      (node (ref "R1") (pin "1") (pinfunction "1_1") (pintype "passive"))
      (node (ref "R2") (pin "1") (pinfunction "1_1") (pintype "passive"))
      (node (ref "Z1") (pin "2") (pinfunction "2_2") (pintype "passive"))
      (node (ref "Z2") (pin "2") (pinfunction "2_2") (pintype "passive"))
    )
    (net (code "58") (name "Net-(JP3-V+[3])") (class "Default")
      (node (ref "JP3") (pin "3") (pinfunction "V+[3]_3") (pintype "passive"))
      (node (ref "U1") (pin "P$9") (pinfunction "V+_P$9") (pintype "bidirectional"))
    )
    (net (code "59") (name "Net-(JP3-V-[2])") (class "Default")
      (node (ref "JP3") (pin "2") (pinfunction "V-[2]_2") (pintype "passive"))
      (node (ref "U1") (pin "P$10") (pinfunction "V-_P$10") (pintype "bidirectional"))
    )
    (net (code "60") (name "Net-(LED5-PadC)") (class "Default")
      (node (ref "LED5") (pin "C") (pinfunction "C_C") (pintype "passive"))
      (node (ref "RN3") (pin "1") (pinfunction "1_1") (pintype "passive"))
    )
    (net (code "61") (name "Net-(LED10-PadC)") (class "Default")
      (node (ref "LED10") (pin "C") (pinfunction "C_C") (pintype "passive"))
      (node (ref "R8") (pin "2") (pinfunction "2_2") (pintype "passive"))
    )
    (net (code "62") (name "Net-(P4-CS)") (class "Default")
      (node (ref "P4") (pin "2") (pinfunction "CS_2") (pintype "bidirectional"))
      (node (ref "RN6") (pin "4") (pinfunction "1_4") (pintype "passive"))
      (node (ref "RN8") (pin "8") (pinfunction "2_8") (pintype "passive"))
    )
    (net (code "63") (name "Net-(P4-DI)") (class "Default")
      (node (ref "P4") (pin "3") (pinfunction "DI_3") (pintype "bidirectional"))
      (node (ref "RN6") (pin "3") (pinfunction "1_3") (pintype "passive"))
      (node (ref "RN8") (pin "6") (pinfunction "2_6") (pintype "passive"))
    )
    (net (code "64") (name "Net-(P4-SCK)") (class "Default")
      (node (ref "P4") (pin "5") (pinfunction "SCK_5") (pintype "bidirectional"))
      (node (ref "RN6") (pin "2") (pinfunction "1_2") (pintype "passive"))
      (node (ref "RN8") (pin "7") (pinfunction "2_7") (pintype "passive"))
    )
    (net (code "65") (name "Net-(Q2-D)") (class "Default")
      (node (ref "Q2") (pin "3") (pinfunction "D_3") (pintype "passive"))
      (node (ref "R8") (pin "1") (pinfunction "1_1") (pintype "passive"))
    )
    (net (code "66") (name "Net-(R6-Pad2)") (class "Default")
      (node (ref "R6") (pin "2") (pinfunction "2_2") (pintype "passive"))
      (node (ref "R7") (pin "1") (pinfunction "1_1") (pintype "passive"))
    )
    (net (code "67") (name "Net-(RN1B-2)") (class "Default")
      (node (ref "LED3") (pin "C") (pinfunction "C_C") (pintype "passive"))
      (node (ref "RN1") (pin "7") (pinfunction "2_7") (pintype "passive"))
    )
    (net (code "68") (name "Net-(RN1C-2)") (class "Default")
      (node (ref "LED4") (pin "C") (pinfunction "C_C") (pintype "passive"))
      (node (ref "RN1") (pin "6") (pinfunction "2_6") (pintype "passive"))
    )
    (net (code "69") (name "Net-(RN1D-2)") (class "Default")
      (node (ref "LED7") (pin "C") (pinfunction "C_C") (pintype "passive"))
      (node (ref "RN1") (pin "5") (pinfunction "2_5") (pintype "passive"))
    )
    (net (code "70") (name "Net-(RN2B-1)") (class "Default")
      (node (ref "RN2") (pin "2") (pinfunction "1_2") (pintype "passive"))
      (node (ref "U1") (pin "P$12") (pinfunction "Y-_P$12") (pintype "bidirectional"))
    )
    (net (code "71") (name "Net-(RN2C-2)") (class "Default")
      (node (ref "LED8") (pin "C") (pinfunction "C_C") (pintype "passive"))
      (node (ref "RN2") (pin "6") (pinfunction "2_6") (pintype "passive"))
    )
    (net (code "72") (name "Net-(RN2D-2)") (class "Default")
      (node (ref "LED9") (pin "C") (pinfunction "C_C") (pintype "passive"))
      (node (ref "RN2") (pin "5") (pinfunction "2_5") (pintype "passive"))
    )
    (net (code "73") (name "Net-(RN3B-1)") (class "Default")
      (node (ref "LED6") (pin "C") (pinfunction "C_C") (pintype "passive"))
      (node (ref "RN3") (pin "2") (pinfunction "1_2") (pintype "passive"))
    )
    (net (code "74") (name "Net-(RN5A-2)") (class "Default")
      (node (ref "C23") (pin "1") (pinfunction "1_1") (pintype "passive"))
      (node (ref "RN5") (pin "7") (pinfunction "2_7") (pintype "passive"))
      (node (ref "RN5") (pin "8") (pinfunction "2_8") (pintype "passive"))
    )
    (net (code "75") (name "Net-(RN5C-2)") (class "Default")
      (node (ref "C24") (pin "1") (pinfunction "1_1") (pintype "passive"))
      (node (ref "RN5") (pin "5") (pinfunction "2_5") (pintype "passive"))
      (node (ref "RN5") (pin "6") (pinfunction "2_6") (pintype "passive"))
    )
    (net (code "76") (name "Net-(RN6A-2)") (class "Default")
      (node (ref "LED2") (pin "C") (pinfunction "C_C") (pintype "passive"))
      (node (ref "RN6") (pin "8") (pinfunction "2_8") (pintype "passive"))
    )
    (net (code "77") (name "Net-(RN6D-2)") (class "Default")
      (node (ref "RN6") (pin "5") (pinfunction "2_5") (pintype "passive"))
      (node (ref "SJ7") (pin "1") (pinfunction "1_1") (pintype "passive"))
    )
    (net (code "78") (name "Net-(U1-G-)") (class "Default")
      (node (ref "RN2") (pin "1") (pinfunction "1_1") (pintype "passive"))
      (node (ref "U1") (pin "P$14") (pinfunction "G-_P$14") (pintype "bidirectional"))
    )
    (net (code "79") (name "RESET") (class "Default")
      (node (ref "C19") (pin "2") (pinfunction "2_2") (pintype "passive"))
      (node (ref "H2") (pin "3") (pinfunction "3_3") (pintype "passive"))
      (node (ref "IC5") (pin "29") (pinfunction "PC6(/RESET)_29") (pintype "bidirectional"))
      (node (ref "IC6") (pin "48") (pinfunction "~{RESET}_48") (pintype "bidirectional"))
      (node (ref "P2") (pin "5") (pinfunction "5_5") (pintype "passive"))
      (node (ref "RN4") (pin "2") (pinfunction "1_2") (pintype "passive"))
      (node (ref "S1") (pin "3") (pinfunction "3_3") (pintype "passive"))
      (node (ref "S1") (pin "4") (pinfunction "4_4") (pintype "passive"))
    )
    (net (code "80") (name "RXIN") (class "Default")
      (node (ref "IC6") (pin "5") (pinfunction "RXIN_5") (pintype "bidirectional"))
      (node (ref "RN5") (pin "2") (pinfunction "1_2") (pintype "passive"))
      (node (ref "U1") (pin "P$2") (pinfunction "RX-_P$2") (pintype "bidirectional"))
    )
    (net (code "81") (name "RXIP") (class "Default")
      (node (ref "IC6") (pin "6") (pinfunction "RXIP_6") (pintype "bidirectional"))
      (node (ref "RN5") (pin "1") (pinfunction "1_1") (pintype "passive"))
      (node (ref "U1") (pin "P$1") (pinfunction "RX+_P$1") (pintype "bidirectional"))
    )
    (net (code "82") (name "RX_LED") (class "Default")
      (node (ref "IC2") (pin "13") (pinfunction "GPIO_1_13") (pintype "bidirectional"))
      (node (ref "RN3") (pin "7") (pinfunction "2_7") (pintype "passive"))
    )
    (net (code "83") (name "SPDLED") (class "Default")
      (node (ref "IC6") (pin "18") (pinfunction "~{SPD}_18") (pintype "bidirectional"))
      (node (ref "RN2") (pin "3") (pinfunction "1_3") (pintype "passive"))
    )
    (net (code "84") (name "TXON") (class "Default")
      (node (ref "IC6") (pin "2") (pinfunction "TXON_2") (pintype "bidirectional"))
      (node (ref "RN5") (pin "4") (pinfunction "1_4") (pintype "passive"))
      (node (ref "U1") (pin "P$6") (pinfunction "TX-_P$6") (pintype "bidirectional"))
    )
    (net (code "85") (name "TXOP") (class "Default")
      (node (ref "IC6") (pin "3") (pinfunction "TXOP_3") (pintype "bidirectional"))
      (node (ref "RN5") (pin "3") (pinfunction "1_3") (pintype "passive"))
      (node (ref "U1") (pin "P$5") (pinfunction "TX+_P$5") (pintype "bidirectional"))
    )
    (net (code "86") (name "TX_LED") (class "Default")
      (node (ref "IC2") (pin "14") (pinfunction "GPIO_0_14") (pintype "bidirectional"))
      (node (ref "RN3") (pin "8") (pinfunction "2_8") (pintype "passive"))
    )
    (net (code "87") (name "USBGND") (class "Default")
      (node (ref "L3") (pin "2") (pinfunction "2_2") (pintype "passive"))
      (node (ref "SJ1") (pin "1") (pinfunction "1_1") (pintype "passive"))
    )
    (net (code "88") (name "USBRXD") (class "Default")
      (node (ref "IC2") (pin "21") (pinfunction "TXD_21") (pintype "output"))
      (node (ref "RN3") (pin "5") (pinfunction "2_5") (pintype "passive"))
    )
    (net (code "89") (name "USBTXD") (class "Default")
      (node (ref "IC2") (pin "20") (pinfunction "RXD_20") (pintype "input"))
      (node (ref "RN3") (pin "6") (pinfunction "2_6") (pintype "passive"))
    )
    (net (code "90") (name "USBVCC") (class "Default")
      (node (ref "F1") (pin "2") (pinfunction "2_2") (pintype "passive"))
      (node (ref "Q1") (pin "3") (pinfunction "D_3") (pintype "passive"))
    )
    (net (code "91") (name "VIN") (class "Default")
      (node (ref "C5") (pin "+") (pinfunction "+_+") (pintype "passive"))
      (node (ref "D1") (pin "C") (pinfunction "C_C") (pintype "passive"))
      (node (ref "H2") (pin "8") (pinfunction "8_8") (pintype "passive"))
      (node (ref "IC1") (pin "3") (pinfunction "VI_3") (pintype "input"))
      (node (ref "JP3") (pin "4") (pinfunction "VIN[4]_4") (pintype "passive"))
      (node (ref "RN4") (pin "3") (pinfunction "1_3") (pintype "passive"))
    )
    (net (code "92") (name "unconnected-(H2-Pad1)") (class "Default")
      (node (ref "H2") (pin "1") (pinfunction "1_1") (pintype "passive"))
    )
    (net (code "93") (name "unconnected-(IC2-CTS-Pad18)") (class "Default")
      (node (ref "IC2") (pin "18") (pinfunction "CTS_18") (pintype "input"))
    )
    (net (code "94") (name "unconnected-(IC2-DCD-Pad24)") (class "Default")
      (node (ref "IC2") (pin "24") (pinfunction "DCD_24") (pintype "input"))
    )
    (net (code "95") (name "unconnected-(IC2-DSR-Pad22)") (class "Default")
      (node (ref "IC2") (pin "22") (pinfunction "DSR_22") (pintype "input"))
    )
    (net (code "96") (name "unconnected-(IC2-GPIO_2-Pad12)") (class "Default")
      (node (ref "IC2") (pin "12") (pinfunction "GPIO_2_12") (pintype "bidirectional"))
    )
    (net (code "97") (name "unconnected-(IC2-GPIO_3-Pad11)") (class "Default")
      (node (ref "IC2") (pin "11") (pinfunction "GPIO_3_11") (pintype "bidirectional"))
    )
    (net (code "98") (name "unconnected-(IC2-NC-Pad10)") (class "Default")
      (node (ref "IC2") (pin "10") (pinfunction "NC_10") (pintype "input"))
    )
    (net (code "99") (name "unconnected-(IC2-RI-Pad1)") (class "Default")
      (node (ref "IC2") (pin "1") (pinfunction "RI_1") (pintype "input"))
    )
    (net (code "100") (name "unconnected-(IC2-RTS-Pad19)") (class "Default")
      (node (ref "IC2") (pin "19") (pinfunction "RTS_19") (pintype "output"))
    )
    (net (code "101") (name "unconnected-(IC2-SUSPEND-Pad17)") (class "Default")
      (node (ref "IC2") (pin "17") (pinfunction "SUSPEND_17") (pintype "output"))
    )
    (net (code "102") (name "unconnected-(IC2-VPP-Pad16)") (class "Default")
      (node (ref "IC2") (pin "16") (pinfunction "VPP_16") (pintype "bidirectional"))
    )
    (net (code "103") (name "unconnected-(IC2-~{RST}-Pad9)") (class "Default")
      (node (ref "IC2") (pin "9") (pinfunction "~{RST}_9") (pintype "bidirectional"))
    )
    (net (code "104") (name "unconnected-(IC2-~{SUSPEND}-Pad15)") (class "Default")
      (node (ref "IC2") (pin "15") (pinfunction "~{SUSPEND}_15") (pintype "output"))
    )
    (net (code "105") (name "unconnected-(IC6-DAT0-Pad37)") (class "Default")
      (node (ref "IC6") (pin "37") (pinfunction "DAT0_37") (pintype "bidirectional"))
    )
    (net (code "106") (name "unconnected-(IC6-DAT1-Pad38)") (class "Default")
      (node (ref "IC6") (pin "38") (pinfunction "DAT1_38") (pintype "bidirectional"))
    )
    (net (code "107") (name "unconnected-(IC6-DAT2-Pad39)") (class "Default")
      (node (ref "IC6") (pin "39") (pinfunction "DAT2_39") (pintype "bidirectional"))
    )
    (net (code "108") (name "unconnected-(IC6-DAT3-Pad40)") (class "Default")
      (node (ref "IC6") (pin "40") (pinfunction "DAT3_40") (pintype "bidirectional"))
    )
    (net (code "109") (name "unconnected-(IC6-DAT4-Pad41)") (class "Default")
      (node (ref "IC6") (pin "41") (pinfunction "DAT4_41") (pintype "bidirectional"))
    )
    (net (code "110") (name "unconnected-(IC6-DAT5-Pad42)") (class "Default")
      (node (ref "IC6") (pin "42") (pinfunction "DAT5_42") (pintype "bidirectional"))
    )
    (net (code "111") (name "unconnected-(IC6-DAT6-Pad43)") (class "Default")
      (node (ref "IC6") (pin "43") (pinfunction "DAT6_43") (pintype "bidirectional"))
    )
    (net (code "112") (name "unconnected-(IC6-DAT7-Pad44)") (class "Default")
      (node (ref "IC6") (pin "44") (pinfunction "DAT7_44") (pintype "bidirectional"))
    )
    (net (code "113") (name "unconnected-(IC6-~{RD}-Pad34)") (class "Default")
      (node (ref "IC6") (pin "34") (pinfunction "~{RD}_34") (pintype "bidirectional"))
    )
    (net (code "114") (name "unconnected-(IC6-~{WR}-Pad35)") (class "Default")
      (node (ref "IC6") (pin "35") (pinfunction "~{WR}_35") (pintype "bidirectional"))
    )
    (net (code "115") (name "unconnected-(J2-SBU1-PadA8)") (class "Default")
      (node (ref "J2") (pin "A8") (pinfunction "SBU1_A8") (pintype "bidirectional"))
    )
    (net (code "116") (name "unconnected-(J2-SBU2-PadB8)") (class "Default")
      (node (ref "J2") (pin "B8") (pinfunction "SBU2_B8") (pintype "bidirectional"))
    )
    (net (code "117") (name "unconnected-(JP3-PadMNT1)") (class "Default")
      (node (ref "JP3") (pin "MNT1") (pinfunction "MNT1_MNT1") (pintype "passive"))
    )
    (net (code "118") (name "unconnected-(JP3-PadMNT2)") (class "Default")
      (node (ref "JP3") (pin "MNT2") (pinfunction "MNT2_MNT2") (pintype "passive"))
    )
    (net (code "119") (name "unconnected-(P4-NC-Pad1)") (class "Default")
      (node (ref "P4") (pin "1") (pinfunction "NC_1") (pintype "bidirectional"))
    )
    (net (code "120") (name "unconnected-(P4-RSV-Pad8)") (class "Default")
      (node (ref "P4") (pin "8") (pinfunction "RSV_8") (pintype "bidirectional"))
    )
    (net (code "121") (name "unconnected-(RN1-Pad1)") (class "Default")
      (node (ref "RN1") (pin "1") (pinfunction "1_1") (pintype "passive"))
    )
    (net (code "122") (name "unconnected-(RN1A-2-Pad8)") (class "Default")
      (node (ref "RN1") (pin "8") (pinfunction "2_8") (pintype "passive"))
    )
    (net (code "123") (name "unconnected-(RN4-Pad1)") (class "Default")
      (node (ref "RN4") (pin "1") (pinfunction "1_1") (pintype "passive"))
    )
    (net (code "124") (name "unconnected-(RN4A-2-Pad8)") (class "Default")
      (node (ref "RN4") (pin "8") (pinfunction "2_8") (pintype "passive"))
    )
    (net (code "125") (name "unconnected-(RN8D-1-Pad4)") (class "Default")
      (node (ref "RN8") (pin "4") (pinfunction "1_4") (pintype "passive"))
    )
    (net (code "126") (name "unconnected-(RN8D-2-Pad5)") (class "Default")
      (node (ref "RN8") (pin "5") (pinfunction "2_5") (pintype "passive"))
    )
  )
)
